# USBDroidR3.net
KiCad netlist of a schematic drawn in EAGLE
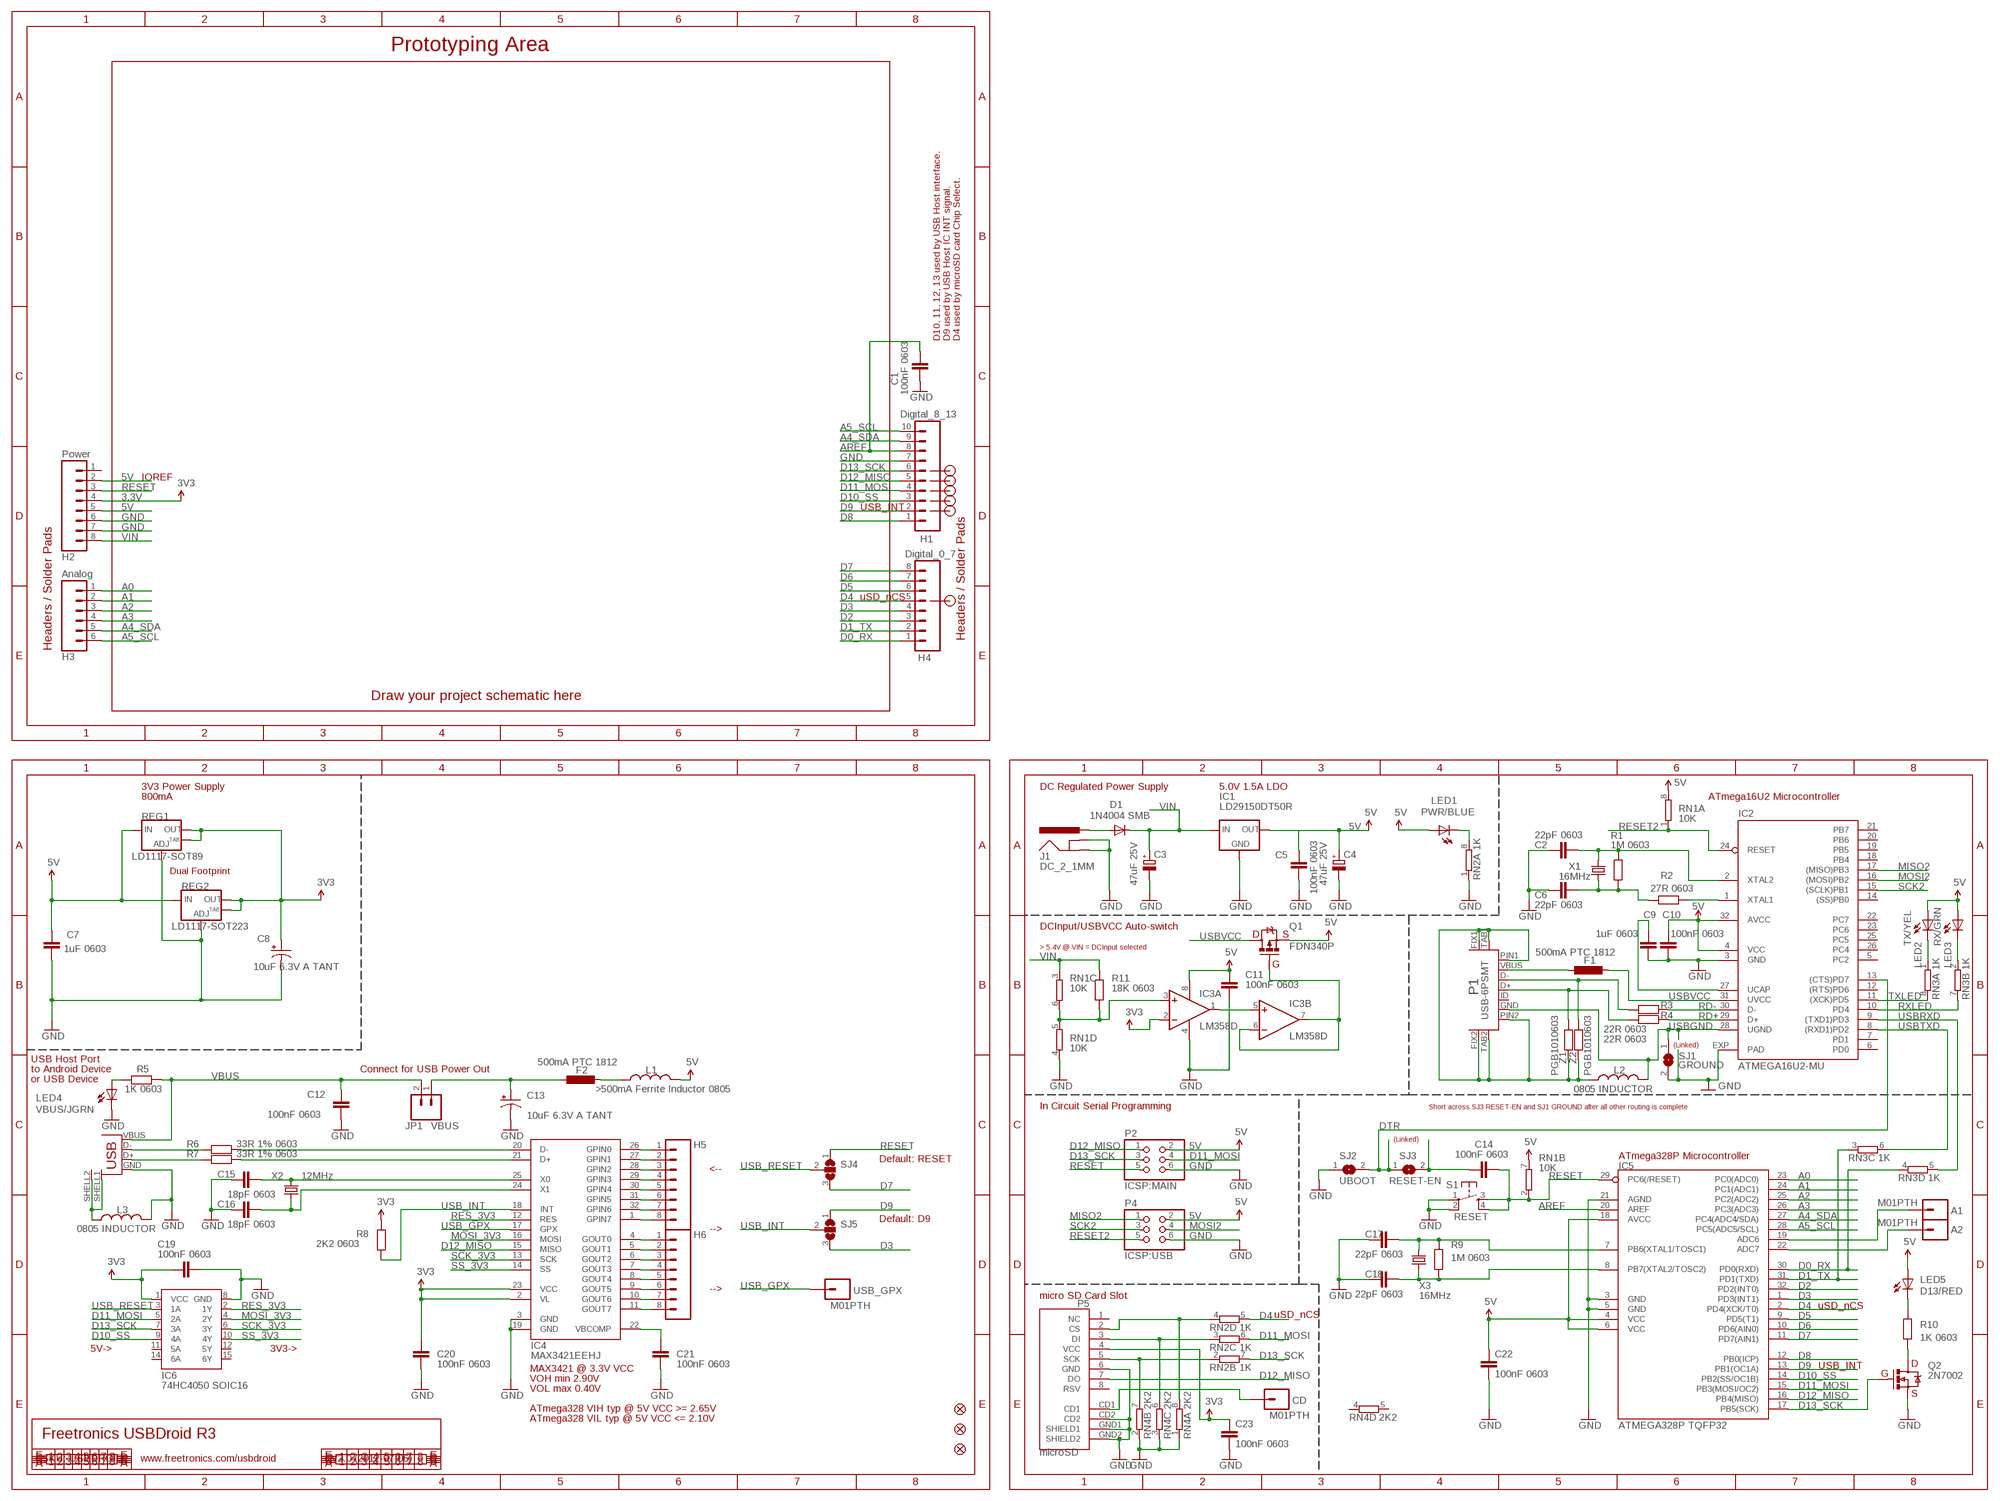
[diagram p0: schematic, sheet 1]

(export (version "E")
  (design (tool "Eeschema 10.0.6"))
  (components
    (comp (ref "A1")
      (value "M01PTH")
      (footprint "eagle-import:1X01")
      (libsource (lib "eagle-import") (part "M01PTH"))
    )
    (comp (ref "A2")
      (value "M01PTH")
      (footprint "eagle-import:1X01")
      (libsource (lib "eagle-import") (part "M01PTH"))
    )
    (comp (ref "C1")
      (value "100nF 0603")
      (footprint "eagle-import:0603")
      (libsource (lib "eagle-import") (part "CAP0603"))
    )
    (comp (ref "C2")
      (value "22pF 0603")
      (footprint "eagle-import:0603")
      (libsource (lib "eagle-import") (part "CAP0603"))
    )
    (comp (ref "C3")
      (value "47uF 25V")
      (footprint "eagle-import:PANASONIC_D")
      (libsource (lib "eagle-import") (part "CPOL-EUD"))
    )
    (comp (ref "C4")
      (value "47uF 25V")
      (footprint "eagle-import:PANASONIC_D")
      (libsource (lib "eagle-import") (part "CPOL-EUD"))
    )
    (comp (ref "C5")
      (value "100nF 0603")
      (footprint "eagle-import:0603")
      (libsource (lib "eagle-import") (part "CAP0603"))
    )
    (comp (ref "C6")
      (value "22pF 0603")
      (footprint "eagle-import:0603")
      (libsource (lib "eagle-import") (part "CAP0603"))
    )
    (comp (ref "C7")
      (value "1uF 0603")
      (footprint "eagle-import:0603")
      (libsource (lib "eagle-import") (part "CAP0603"))
    )
    (comp (ref "C8")
      (value "10uF 6.3V A TANT")
      (footprint "eagle-import:EIA3216")
      (libsource (lib "eagle-import") (part "CAP_POL1206"))
    )
    (comp (ref "C9")
      (value "1uF 0603")
      (footprint "eagle-import:0603")
      (libsource (lib "eagle-import") (part "CAP0603"))
    )
    (comp (ref "C10")
      (value "100nF 0603")
      (footprint "eagle-import:0603")
      (libsource (lib "eagle-import") (part "CAP0603"))
    )
    (comp (ref "C11")
      (value "100nF 0603")
      (footprint "eagle-import:0603")
      (libsource (lib "eagle-import") (part "CAP0603"))
    )
    (comp (ref "C12")
      (value "100nF 0603")
      (footprint "eagle-import:0603")
      (libsource (lib "eagle-import") (part "CAP0603"))
    )
    (comp (ref "C13")
      (value "10uF 6.3V A TANT")
      (footprint "eagle-import:EIA3216")
      (libsource (lib "eagle-import") (part "CAP_POL1206"))
    )
    (comp (ref "C14")
      (value "100nF 0603")
      (footprint "eagle-import:0603")
      (libsource (lib "eagle-import") (part "CAP0603"))
    )
    (comp (ref "C15")
      (value "18pF 0603")
      (footprint "eagle-import:0603")
      (libsource (lib "eagle-import") (part "CAP0603"))
    )
    (comp (ref "C16")
      (value "18pF 0603")
      (footprint "eagle-import:0603")
      (libsource (lib "eagle-import") (part "CAP0603"))
    )
    (comp (ref "C17")
      (value "22pF 0603")
      (footprint "eagle-import:0603")
      (libsource (lib "eagle-import") (part "CAP0603"))
    )
    (comp (ref "C18")
      (value "22pF 0603")
      (footprint "eagle-import:0603")
      (libsource (lib "eagle-import") (part "CAP0603"))
    )
    (comp (ref "C19")
      (value "100nF 0603")
      (footprint "eagle-import:0603")
      (libsource (lib "eagle-import") (part "CAP0603"))
    )
    (comp (ref "C20")
      (value "100nF 0603")
      (footprint "eagle-import:0603")
      (libsource (lib "eagle-import") (part "CAP0603"))
    )
    (comp (ref "C21")
      (value "100nF 0603")
      (footprint "eagle-import:0603")
      (libsource (lib "eagle-import") (part "CAP0603"))
    )
    (comp (ref "C22")
      (value "100nF 0603")
      (footprint "eagle-import:0603")
      (libsource (lib "eagle-import") (part "CAP0603"))
    )
    (comp (ref "C23")
      (value "100nF 0603")
      (footprint "eagle-import:0603")
      (libsource (lib "eagle-import") (part "CAP0603"))
    )
    (comp (ref "CD")
      (value "M01PTH")
      (footprint "eagle-import:1X01")
      (libsource (lib "eagle-import") (part "M01PTH"))
    )
    (comp (ref "D1")
      (value "1N4004 SMB")
      (footprint "eagle-import:SMB-DIODE")
      (libsource (lib "eagle-import") (part "DIODESMB"))
    )
    (comp (ref "F1")
      (value "500mA PTC 1812")
      (footprint "eagle-import:L1812")
      (libsource (lib "eagle-import") (part "L-EUL1812"))
    )
    (comp (ref "F2")
      (value "500mA PTC 1812")
      (footprint "eagle-import:L1812")
      (libsource (lib "eagle-import") (part "L-EUL1812"))
    )
    (comp (ref "FID1")
      (value "FIDUCIAL1X2.5")
      (footprint "eagle-import:FIDUCIAL-1X2.5")
      (libsource (lib "eagle-import") (part "FIDUCIAL1X2.5"))
    )
    (comp (ref "FID2")
      (value "FIDUCIAL1X2.5")
      (footprint "eagle-import:FIDUCIAL-1X2.5")
      (libsource (lib "eagle-import") (part "FIDUCIAL1X2.5"))
    )
    (comp (ref "FID3")
      (value "FIDUCIAL1X2.5")
      (footprint "eagle-import:FIDUCIAL-1X2.5")
      (libsource (lib "eagle-import") (part "FIDUCIAL1X2.5"))
    )
    (comp (ref "H1")
      (value "Digital_8_13")
      (footprint "eagle-import:1X10")
      (libsource (lib "eagle-import") (part "M100.1"))
    )
    (comp (ref "H2")
      (value "Power")
      (footprint "eagle-import:1X08")
      (libsource (lib "eagle-import") (part "freetronics-master-v1_M08"))
    )
    (comp (ref "H3")
      (value "Analog")
      (footprint "eagle-import:1X06")
      (libsource (lib "eagle-import") (part "M06SIP"))
    )
    (comp (ref "H4")
      (value "Digital_0_7")
      (footprint "eagle-import:1X08")
      (libsource (lib "eagle-import") (part "M08"))
    )
    (comp (ref "H5")
      (value "GPIN")
      (footprint "eagle-import:1X08")
      (libsource (lib "eagle-import") (part "M08"))
    )
    (comp (ref "H6")
      (value "GPIN")
      (footprint "eagle-import:1X08")
      (libsource (lib "eagle-import") (part "M08"))
    )
    (comp (ref "IC1")
      (value "LD29150DT50R")
      (footprint "eagle-import:DPACK")
      (libsource (lib "eagle-import") (part "V_REG_78XX"))
    )
    (comp (ref "IC2")
      (value "ATMEGA16U2-MU")
      (footprint "eagle-import:ATMEL_QFN32")
      (libsource (lib "eagle-import") (part "ATMEL_ATMEGA8U2-MUQFN"))
    )
    (comp (ref "IC3")
      (value "LM358D")
      (footprint "eagle-import:SO08")
      (libsource (lib "eagle-import") (part "LM358D"))
    )
    (comp (ref "IC4")
      (value "MAX3421EEHJ")
      (footprint "eagle-import:TQFP32-5MM")
      (libsource (lib "eagle-import") (part "MAX3421ESMD"))
    )
    (comp (ref "IC5")
      (value "ATMEGA328P TQFP32")
      (footprint "eagle-import:TQFP32-08")
      (libsource (lib "eagle-import") (part "AVR-MEGA8-AI"))
    )
    (comp (ref "IC6")
      (value "74HC4050 SOIC16")
      (footprint "eagle-import:SO016")
      (libsource (lib "eagle-import") (part "HEX_CONVERTER"))
    )
    (comp (ref "J1")
      (value "DC_2_1MM")
      (footprint "eagle-import:POWER_JACK_PTH")
      (libsource (lib "eagle-import") (part "POWER_JACKPTH"))
    )
    (comp (ref "JP1")
      (value "VBUS")
      (footprint "eagle-import:1X02_LOCK")
      (libsource (lib "eagle-import") (part "M02LOCK"))
    )
    (comp (ref "L1")
      (value ">500mA Ferrite Inductor 0805")
      (footprint "eagle-import:0805-LARGE")
      (libsource (lib "eagle-import") (part "INDUCTOR0805-LARGE"))
    )
    (comp (ref "L2")
      (value "0805 INDUCTOR")
      (footprint "eagle-import:0805-LARGE")
      (libsource (lib "eagle-import") (part "INDUCTOR0805-LARGE"))
    )
    (comp (ref "L3")
      (value "0805 INDUCTOR")
      (footprint "eagle-import:0805-LARGE")
      (libsource (lib "eagle-import") (part "INDUCTOR0805-LARGE"))
    )
    (comp (ref "LED1")
      (value "PWR/BLUE")
      (footprint "eagle-import:LED-0603")
      (libsource (lib "eagle-import") (part "LED0603"))
    )
    (comp (ref "LED2")
      (value "TX/YEL")
      (footprint "eagle-import:LED-0603")
      (libsource (lib "eagle-import") (part "LED0603"))
    )
    (comp (ref "LED3")
      (value "RX/GRN")
      (footprint "eagle-import:LED-0603")
      (libsource (lib "eagle-import") (part "LED0603"))
    )
    (comp (ref "LED4")
      (value "VBUS/JGRN")
      (footprint "eagle-import:LED-0603")
      (libsource (lib "eagle-import") (part "LED0603"))
    )
    (comp (ref "LED5")
      (value "D13/RED")
      (footprint "eagle-import:LED-0603")
      (libsource (lib "eagle-import") (part "LED0603"))
    )
    (comp (ref "P1")
      (value "USB-6PSMT")
      (footprint "eagle-import:USB-MICROB-MB05PMXX")
      (libsource (lib "eagle-import") (part "USB-6PSMT"))
    )
    (comp (ref "P2")
      (value "ICSP:MAIN")
      (footprint "eagle-import:2X03")
      (libsource (lib "eagle-import") (part "PINHD-2X3"))
    )
    (comp (ref "P3")
      (value "USB_")
      (footprint "eagle-import:USB-A-S-SILK-FEMALE")
      (libsource (lib "eagle-import") (part "USB_"))
    )
    (comp (ref "P4")
      (value "ICSP:USB")
      (footprint "eagle-import:2X03")
      (libsource (lib "eagle-import") (part "PINHD-2X3"))
    )
    (comp (ref "P5")
      (value "microSD")
      (footprint "eagle-import:MICRO-SD-SOCKET-PP")
      (libsource (lib "eagle-import") (part "USD-SOCKETNEW"))
    )
    (comp (ref "Q1")
      (value "FDN340P")
      (footprint "eagle-import:SOT23")
      (libsource (lib "eagle-import") (part "MOSFET-PCHANNEL"))
    )
    (comp (ref "Q2")
      (value "2N7002")
      (footprint "eagle-import:SOT23-3")
      (libsource (lib "eagle-import") (part "MOSFET-NCHANNELSMD"))
    )
    (comp (ref "R1")
      (value "1M 0603")
      (footprint "eagle-import:0603")
      (libsource (lib "eagle-import") (part "RESISTOR0603"))
    )
    (comp (ref "R2")
      (value "27R 0603")
      (footprint "eagle-import:0603")
      (libsource (lib "eagle-import") (part "RESISTOR0603"))
    )
    (comp (ref "R3")
      (value "22R 0603")
      (footprint "eagle-import:0603")
      (libsource (lib "eagle-import") (part "RESISTOR0603"))
    )
    (comp (ref "R4")
      (value "22R 0603")
      (footprint "eagle-import:0603")
      (libsource (lib "eagle-import") (part "RESISTOR0603"))
    )
    (comp (ref "R5")
      (value "1K 0603")
      (footprint "eagle-import:0603")
      (libsource (lib "eagle-import") (part "RESISTOR0603"))
    )
    (comp (ref "R6")
      (value "33R 1% 0603")
      (footprint "eagle-import:0603")
      (libsource (lib "eagle-import") (part "RESISTOR0603"))
    )
    (comp (ref "R7")
      (value "33R 1% 0603")
      (footprint "eagle-import:0603")
      (libsource (lib "eagle-import") (part "RESISTOR0603"))
    )
    (comp (ref "R8")
      (value "2K2 0603")
      (footprint "eagle-import:0603")
      (libsource (lib "eagle-import") (part "RESISTOR0603"))
    )
    (comp (ref "R9")
      (value "1M 0603")
      (footprint "eagle-import:0603")
      (libsource (lib "eagle-import") (part "RESISTOR0603"))
    )
    (comp (ref "R10")
      (value "1K 0603")
      (footprint "eagle-import:0603")
      (libsource (lib "eagle-import") (part "RESISTOR0603"))
    )
    (comp (ref "R11")
      (value "18K 0603")
      (footprint "eagle-import:0603")
      (libsource (lib "eagle-import") (part "RESISTOR0603"))
    )
    (comp (ref "REG1")
      (value "LD1117-SOT89")
      (footprint "eagle-import:SOT89")
      (libsource (lib "eagle-import") (part "V_REG_LM1117SOT89"))
    )
    (comp (ref "REG2")
      (value "LD1117-SOT223")
      (footprint "eagle-import:SOT223")
      (libsource (lib "eagle-import") (part "V_REG_LM1117SOT223"))
    )
    (comp (ref "RN1")
      (value "10K")
      (footprint "eagle-import:CAY16")
      (libsource (lib "eagle-import") (part "4R-NCAY16"))
    )
    (comp (ref "RN2")
      (value "1K")
      (footprint "eagle-import:CAY16")
      (libsource (lib "eagle-import") (part "4R-NCAY16"))
    )
    (comp (ref "RN3")
      (value "1K")
      (footprint "eagle-import:CAY16")
      (libsource (lib "eagle-import") (part "4R-NCAY16"))
    )
    (comp (ref "RN4")
      (value "2K2")
      (footprint "eagle-import:CAY16")
      (libsource (lib "eagle-import") (part "4R-NCAY16"))
    )
    (comp (ref "S1")
      (value "RESET")
      (footprint "eagle-import:TACTILE_SWITCH_SMD")
      (libsource (lib "eagle-import") (part "TAC_SWITCHSMD"))
    )
    (comp (ref "SJ1")
      (value "GROUND")
      (footprint "eagle-import:SJ")
      (libsource (lib "eagle-import") (part "SJ"))
    )
    (comp (ref "SJ2")
      (value "UBOOT")
      (footprint "eagle-import:SJ")
      (libsource (lib "eagle-import") (part "SJ"))
    )
    (comp (ref "SJ3")
      (value "RESET-EN")
      (footprint "eagle-import:SJ")
      (libsource (lib "eagle-import") (part "SJ"))
    )
    (comp (ref "SJ4")
      (value "SJ2W")
      (footprint "eagle-import:SJ_2")
      (libsource (lib "eagle-import") (part "SJ2W"))
    )
    (comp (ref "SJ5")
      (value "SJ2W")
      (footprint "eagle-import:SJ_2")
      (libsource (lib "eagle-import") (part "SJ2W"))
    )
    (comp (ref "USB_GPX")
      (value "M01PTH")
      (footprint "eagle-import:1X01")
      (libsource (lib "eagle-import") (part "M01PTH"))
    )
    (comp (ref "X1")
      (value "16MHz")
      (footprint "eagle-import:HC49U-V")
      (libsource (lib "eagle-import") (part "CRYSTALHC49UV"))
    )
    (comp (ref "X2")
      (value "12MHz")
      (footprint "eagle-import:HC49U-V")
      (libsource (lib "eagle-import") (part "CRYSTALHC49UV"))
    )
    (comp (ref "X3")
      (value "16MHz")
      (footprint "eagle-import:HC49U-V")
      (libsource (lib "eagle-import") (part "CRYSTALHC49UV"))
    )
    (comp (ref "Z1")
      (value "PGB1010603")
      (footprint "eagle-import:0603")
      (libsource (lib "eagle-import") (part "RESISTOR0603"))
    )
    (comp (ref "Z2")
      (value "PGB1010603")
      (footprint "eagle-import:0603")
      (libsource (lib "eagle-import") (part "RESISTOR0603"))
    )
  )
  (nets
    (net (code "1") (name "/A0") (class "Default")
      (node (ref "H3") (pin "1") (pinfunction "1_1") (pintype "passive"))
      (node (ref "IC5") (pin "23") (pinfunction "PC0(ADC0)_23") (pintype "bidirectional"))
    )
    (net (code "2") (name "/A1") (class "Default")
      (node (ref "H3") (pin "2") (pinfunction "2_2") (pintype "passive"))
      (node (ref "IC5") (pin "24") (pinfunction "PC1(ADC1)_24") (pintype "bidirectional"))
    )
    (net (code "3") (name "/A2") (class "Default")
      (node (ref "H3") (pin "3") (pinfunction "3_3") (pintype "passive"))
      (node (ref "IC5") (pin "25") (pinfunction "PC2(ADC2)_25") (pintype "bidirectional"))
    )
    (net (code "4") (name "/A3") (class "Default")
      (node (ref "H3") (pin "4") (pinfunction "4_4") (pintype "passive"))
      (node (ref "IC5") (pin "26") (pinfunction "PC3(ADC3)_26") (pintype "bidirectional"))
    )
    (net (code "5") (name "/A4_SDA") (class "Default")
      (node (ref "H1") (pin "9") (pinfunction "9_9") (pintype "passive"))
      (node (ref "H3") (pin "5") (pinfunction "5_5") (pintype "passive"))
      (node (ref "IC5") (pin "27") (pinfunction "PC4(ADC4/SDA)_27") (pintype "bidirectional"))
    )
    (net (code "6") (name "/A5_SCL") (class "Default")
      (node (ref "H1") (pin "10") (pinfunction "10_10") (pintype "passive"))
      (node (ref "H3") (pin "6") (pinfunction "6_6") (pintype "passive"))
      (node (ref "IC5") (pin "28") (pinfunction "PC5(ADC5/SCL)_28") (pintype "bidirectional"))
    )
    (net (code "7") (name "/AREF") (class "Default")
      (node (ref "C1") (pin "1") (pinfunction "1_1") (pintype "passive"))
      (node (ref "H1") (pin "8") (pinfunction "8_8") (pintype "passive"))
      (node (ref "IC5") (pin "20") (pinfunction "AREF_20") (pintype "bidirectional"))
    )
    (net (code "8") (name "/D0_RX") (class "Default")
      (node (ref "H4") (pin "1") (pinfunction "1_1") (pintype "passive"))
      (node (ref "IC5") (pin "30") (pinfunction "PD0(RXD)_30") (pintype "bidirectional"))
      (node (ref "RN3") (pin "4") (pinfunction "1_4") (pintype "passive"))
    )
    (net (code "9") (name "/D1_TX") (class "Default")
      (node (ref "H4") (pin "2") (pinfunction "2_2") (pintype "passive"))
      (node (ref "IC5") (pin "31") (pinfunction "PD1(TXD)_31") (pintype "bidirectional"))
      (node (ref "RN3") (pin "3") (pinfunction "1_3") (pintype "passive"))
    )
    (net (code "10") (name "/D2") (class "Default")
      (node (ref "H4") (pin "3") (pinfunction "3_3") (pintype "passive"))
      (node (ref "IC5") (pin "32") (pinfunction "PD2(INT0)_32") (pintype "bidirectional"))
    )
    (net (code "11") (name "/D3") (class "Default")
      (node (ref "H4") (pin "4") (pinfunction "4_4") (pintype "passive"))
      (node (ref "IC5") (pin "1") (pinfunction "PD3(INT1)_1") (pintype "bidirectional"))
      (node (ref "SJ5") (pin "3") (pinfunction "3_3") (pintype "passive"))
    )
    (net (code "12") (name "/D4") (class "Default")
      (node (ref "H4") (pin "5") (pinfunction "5_5") (pintype "passive"))
      (node (ref "IC5") (pin "2") (pinfunction "PD4(XCK/T0)_2") (pintype "bidirectional"))
      (node (ref "RN2") (pin "5") (pinfunction "2_5") (pintype "passive"))
    )
    (net (code "13") (name "/D5") (class "Default")
      (node (ref "H4") (pin "6") (pinfunction "6_6") (pintype "passive"))
      (node (ref "IC5") (pin "9") (pinfunction "PD5(T1)_9") (pintype "bidirectional"))
    )
    (net (code "14") (name "/D6") (class "Default")
      (node (ref "H4") (pin "7") (pinfunction "7_7") (pintype "passive"))
      (node (ref "IC5") (pin "10") (pinfunction "PD6(AIN0)_10") (pintype "bidirectional"))
    )
    (net (code "15") (name "/D7") (class "Default")
      (node (ref "H4") (pin "8") (pinfunction "8_8") (pintype "passive"))
      (node (ref "IC5") (pin "11") (pinfunction "PD7(AIN1)_11") (pintype "bidirectional"))
      (node (ref "SJ4") (pin "3") (pinfunction "3_3") (pintype "passive"))
    )
    (net (code "16") (name "/D8") (class "Default")
      (node (ref "H1") (pin "1") (pinfunction "1_1") (pintype "passive"))
      (node (ref "IC5") (pin "12") (pinfunction "PB0(ICP)_12") (pintype "bidirectional"))
    )
    (net (code "17") (name "/D9") (class "Default")
      (node (ref "H1") (pin "2") (pinfunction "2_2") (pintype "passive"))
      (node (ref "IC5") (pin "13") (pinfunction "PB1(OC1A)_13") (pintype "bidirectional"))
      (node (ref "SJ5") (pin "1") (pinfunction "1_1") (pintype "passive"))
    )
    (net (code "18") (name "/D10_SS") (class "Default")
      (node (ref "H1") (pin "3") (pinfunction "3_3") (pintype "passive"))
      (node (ref "IC5") (pin "14") (pinfunction "PB2(SS/OC1B)_14") (pintype "bidirectional"))
      (node (ref "IC6") (pin "9") (pinfunction "4A_9") (pintype "bidirectional"))
    )
    (net (code "19") (name "/D11_MOSI") (class "Default")
      (node (ref "H1") (pin "4") (pinfunction "4_4") (pintype "passive"))
      (node (ref "IC5") (pin "15") (pinfunction "PB3(MOSI/OC2)_15") (pintype "bidirectional"))
      (node (ref "IC6") (pin "5") (pinfunction "2A_5") (pintype "bidirectional"))
      (node (ref "P2") (pin "4") (pinfunction "4_4") (pintype "passive"))
      (node (ref "RN2") (pin "6") (pinfunction "2_6") (pintype "passive"))
    )
    (net (code "20") (name "/D12_MISO") (class "Default")
      (node (ref "H1") (pin "5") (pinfunction "5_5") (pintype "passive"))
      (node (ref "IC4") (pin "15") (pinfunction "MISO_15") (pintype "bidirectional"))
      (node (ref "IC5") (pin "16") (pinfunction "PB4(MISO)_16") (pintype "bidirectional"))
      (node (ref "P2") (pin "1") (pinfunction "1_1") (pintype "passive"))
      (node (ref "P5") (pin "7") (pinfunction "DO_7") (pintype "bidirectional"))
    )
    (net (code "21") (name "/D13_SCK") (class "Default")
      (node (ref "H1") (pin "6") (pinfunction "6_6") (pintype "passive"))
      (node (ref "IC5") (pin "17") (pinfunction "PB5(SCK)_17") (pintype "bidirectional"))
      (node (ref "IC6") (pin "7") (pinfunction "3A_7") (pintype "bidirectional"))
      (node (ref "P2") (pin "3") (pinfunction "3_3") (pintype "passive"))
      (node (ref "Q2") (pin "1") (pinfunction "G_1") (pintype "passive"))
      (node (ref "RN2") (pin "7") (pinfunction "2_7") (pintype "passive"))
    )
    (net (code "22") (name "/DTR") (class "Default")
      (node (ref "IC2") (pin "13") (pinfunction "(CTS)PD7_13") (pintype "bidirectional"))
      (node (ref "SJ2") (pin "2") (pinfunction "2_2") (pintype "passive"))
      (node (ref "SJ3") (pin "1") (pinfunction "1_1") (pintype "passive"))
    )
    (net (code "23") (name "/MISO2") (class "Default")
      (node (ref "IC2") (pin "17") (pinfunction "(MISO)PB3_17") (pintype "bidirectional"))
      (node (ref "P4") (pin "1") (pinfunction "1_1") (pintype "passive"))
    )
    (net (code "24") (name "/MOSI2") (class "Default")
      (node (ref "IC2") (pin "16") (pinfunction "(MOSI)PB2_16") (pintype "bidirectional"))
      (node (ref "P4") (pin "4") (pinfunction "4_4") (pintype "passive"))
    )
    (net (code "25") (name "/MOSI_3V3") (class "Default")
      (node (ref "IC4") (pin "16") (pinfunction "MOSI_16") (pintype "bidirectional"))
      (node (ref "IC6") (pin "4") (pinfunction "2Y_4") (pintype "bidirectional"))
    )
    (net (code "26") (name "/RD+") (class "Default")
      (node (ref "IC2") (pin "29") (pinfunction "D+_29") (pintype "bidirectional"))
      (node (ref "R4") (pin "1") (pinfunction "1_1") (pintype "passive"))
    )
    (net (code "27") (name "/RD-") (class "Default")
      (node (ref "IC2") (pin "30") (pinfunction "D-_30") (pintype "bidirectional"))
      (node (ref "R3") (pin "1") (pinfunction "1_1") (pintype "passive"))
    )
    (net (code "28") (name "/RESET") (class "Default")
      (node (ref "C14") (pin "2") (pinfunction "2_2") (pintype "passive"))
      (node (ref "H2") (pin "3") (pinfunction "3_3") (pintype "passive"))
      (node (ref "IC5") (pin "29") (pinfunction "PC6(/RESET)_29") (pintype "bidirectional"))
      (node (ref "P2") (pin "5") (pinfunction "5_5") (pintype "passive"))
      (node (ref "RN1") (pin "2") (pinfunction "1_2") (pintype "passive"))
      (node (ref "S1") (pin "3") (pinfunction "3_3") (pintype "passive"))
      (node (ref "S1") (pin "4") (pinfunction "4_4") (pintype "passive"))
      (node (ref "SJ4") (pin "1") (pinfunction "1_1") (pintype "passive"))
    )
    (net (code "29") (name "/RESET2") (class "Default")
      (node (ref "IC2") (pin "24") (pinfunction "RESET_24") (pintype "input"))
      (node (ref "P4") (pin "5") (pinfunction "5_5") (pintype "passive"))
      (node (ref "RN1") (pin "1") (pinfunction "1_1") (pintype "passive"))
    )
    (net (code "30") (name "/RES_3V3") (class "Default")
      (node (ref "IC4") (pin "12") (pinfunction "RES_12") (pintype "bidirectional"))
      (node (ref "IC6") (pin "2") (pinfunction "1Y_2") (pintype "bidirectional"))
    )
    (net (code "31") (name "/RXLED") (class "Default")
      (node (ref "IC2") (pin "10") (pinfunction "PD4_10") (pintype "bidirectional"))
      (node (ref "RN3") (pin "7") (pinfunction "2_7") (pintype "passive"))
    )
    (net (code "32") (name "/SCK2") (class "Default")
      (node (ref "IC2") (pin "15") (pinfunction "(SCLK)PB1_15") (pintype "bidirectional"))
      (node (ref "P4") (pin "3") (pinfunction "3_3") (pintype "passive"))
    )
    (net (code "33") (name "/SCK_3V3") (class "Default")
      (node (ref "IC4") (pin "13") (pinfunction "SCK_13") (pintype "bidirectional"))
      (node (ref "IC6") (pin "6") (pinfunction "3Y_6") (pintype "bidirectional"))
    )
    (net (code "34") (name "/SS_3V3") (class "Default")
      (node (ref "IC4") (pin "14") (pinfunction "SS_14") (pintype "bidirectional"))
      (node (ref "IC6") (pin "10") (pinfunction "4Y_10") (pintype "bidirectional"))
    )
    (net (code "35") (name "/TXLED") (class "Default")
      (node (ref "IC2") (pin "11") (pinfunction "(XCK)PD5_11") (pintype "bidirectional"))
      (node (ref "RN3") (pin "8") (pinfunction "2_8") (pintype "passive"))
    )
    (net (code "36") (name "/USBGND") (class "Default")
      (node (ref "IC2") (pin "28") (pinfunction "UGND_28") (pintype "power_in"))
      (node (ref "L2") (pin "2") (pinfunction "2_2") (pintype "passive"))
      (node (ref "P1") (pin "GND") (pinfunction "GND_GND") (pintype "bidirectional"))
      (node (ref "SJ1") (pin "1") (pinfunction "1_1") (pintype "passive"))
    )
    (net (code "37") (name "/USBRXD") (class "Default")
      (node (ref "IC2") (pin "9") (pinfunction "(TXD1)PD3_9") (pintype "bidirectional"))
      (node (ref "RN3") (pin "5") (pinfunction "2_5") (pintype "passive"))
    )
    (net (code "38") (name "/USBTXD") (class "Default")
      (node (ref "IC2") (pin "8") (pinfunction "(RXD1)PD2_8") (pintype "bidirectional"))
      (node (ref "RN3") (pin "6") (pinfunction "2_6") (pintype "passive"))
    )
    (net (code "39") (name "/USBVCC") (class "Default")
      (node (ref "F1") (pin "2") (pinfunction "2_2") (pintype "passive"))
      (node (ref "IC2") (pin "31") (pinfunction "UVCC_31") (pintype "power_in"))
      (node (ref "Q1") (pin "3") (pinfunction "D_3") (pintype "passive"))
    )
    (net (code "40") (name "/USB_GPX") (class "Default")
      (node (ref "IC4") (pin "17") (pinfunction "GPX_17") (pintype "bidirectional"))
      (node (ref "USB_GPX") (pin "1") (pinfunction "1_1") (pintype "passive"))
    )
    (net (code "41") (name "/USB_INT") (class "Default")
      (node (ref "IC4") (pin "18") (pinfunction "INT_18") (pintype "bidirectional"))
      (node (ref "R8") (pin "2") (pinfunction "2_2") (pintype "passive"))
      (node (ref "SJ5") (pin "2") (pinfunction "2_2") (pintype "passive"))
    )
    (net (code "42") (name "/USB_RESET") (class "Default")
      (node (ref "IC6") (pin "3") (pinfunction "1A_3") (pintype "bidirectional"))
      (node (ref "SJ4") (pin "2") (pinfunction "2_2") (pintype "passive"))
    )
    (net (code "43") (name "/VBUS") (class "Default")
      (node (ref "C12") (pin "2") (pinfunction "2_2") (pintype "passive"))
      (node (ref "JP1") (pin "2") (pinfunction "2_2") (pintype "passive"))
      (node (ref "P3") (pin "VBUS") (pinfunction "VBUS_VBUS") (pintype "bidirectional"))
      (node (ref "R5") (pin "2") (pinfunction "2_2") (pintype "passive"))
    )
    (net (code "44") (name "/VIN") (class "Default")
      (node (ref "C3") (pin "+") (pinfunction "+_+") (pintype "passive"))
      (node (ref "D1") (pin "C") (pinfunction "C_C") (pintype "passive"))
      (node (ref "H2") (pin "8") (pinfunction "8_8") (pintype "passive"))
      (node (ref "IC1") (pin "1") (pinfunction "IN_1") (pintype "input"))
      (node (ref "R11") (pin "2") (pinfunction "2_2") (pintype "passive"))
      (node (ref "RN1") (pin "3") (pinfunction "1_3") (pintype "passive"))
    )
    (net (code "45") (name "3V3") (class "Default")
      (node (ref "C19") (pin "2") (pinfunction "2_2") (pintype "passive"))
      (node (ref "C20") (pin "2") (pinfunction "2_2") (pintype "passive"))
      (node (ref "C23") (pin "1") (pinfunction "1_1") (pintype "passive"))
      (node (ref "C8") (pin "A") (pinfunction "+_A") (pintype "passive"))
      (node (ref "H2") (pin "4") (pinfunction "4_4") (pintype "passive"))
      (node (ref "IC3") (pin "2") (pinfunction "-IN_2") (pintype "input"))
      (node (ref "IC4") (pin "2") (pinfunction "VL_2") (pintype "bidirectional"))
      (node (ref "IC4") (pin "23") (pinfunction "VCC_23") (pintype "bidirectional"))
      (node (ref "IC6") (pin "1") (pinfunction "VCC_1") (pintype "bidirectional"))
      (node (ref "P5") (pin "4") (pinfunction "VCC_4") (pintype "bidirectional"))
      (node (ref "R8") (pin "1") (pinfunction "1_1") (pintype "passive"))
      (node (ref "REG1") (pin "2") (pinfunction "OUT_2") (pintype "output"))
      (node (ref "REG1") (pin "4") (pinfunction "OUT_4") (pintype "output"))
      (node (ref "REG2") (pin "2") (pinfunction "OUT_2") (pintype "output"))
      (node (ref "REG2") (pin "4") (pinfunction "OUT_4") (pintype "output"))
    )
    (net (code "46") (name "5V") (class "Default")
      (node (ref "C10") (pin "1") (pinfunction "1_1") (pintype "passive"))
      (node (ref "C11") (pin "1") (pinfunction "1_1") (pintype "passive"))
      (node (ref "C22") (pin "1") (pinfunction "1_1") (pintype "passive"))
      (node (ref "C4") (pin "+") (pinfunction "+_+") (pintype "passive"))
      (node (ref "C5") (pin "1") (pinfunction "1_1") (pintype "passive"))
      (node (ref "C7") (pin "1") (pinfunction "1_1") (pintype "passive"))
      (node (ref "H2") (pin "2") (pinfunction "2_2") (pintype "passive"))
      (node (ref "H2") (pin "5") (pinfunction "5_5") (pintype "passive"))
      (node (ref "IC1") (pin "3") (pinfunction "OUT_3") (pintype "output"))
      (node (ref "IC2") (pin "32") (pinfunction "AVCC_32") (pintype "power_in"))
      (node (ref "IC2") (pin "4") (pinfunction "VCC_4") (pintype "power_in"))
      (node (ref "IC3") (pin "8") (pinfunction "V+_8") (pintype "power_in"))
      (node (ref "IC5") (pin "18") (pinfunction "AVCC_18") (pintype "bidirectional"))
      (node (ref "IC5") (pin "4") (pinfunction "VCC_4") (pintype "bidirectional"))
      (node (ref "IC5") (pin "6") (pinfunction "VCC_6") (pintype "bidirectional"))
      (node (ref "L1") (pin "2") (pinfunction "2_2") (pintype "passive"))
      (node (ref "LED1") (pin "A") (pinfunction "A_A") (pintype "passive"))
      (node (ref "LED2") (pin "A") (pinfunction "A_A") (pintype "passive"))
      (node (ref "LED3") (pin "A") (pinfunction "A_A") (pintype "passive"))
      (node (ref "LED5") (pin "A") (pinfunction "A_A") (pintype "passive"))
      (node (ref "P2") (pin "2") (pinfunction "2_2") (pintype "passive"))
      (node (ref "P4") (pin "2") (pinfunction "2_2") (pintype "passive"))
      (node (ref "Q1") (pin "2") (pinfunction "S_2") (pintype "passive"))
      (node (ref "REG1") (pin "3") (pinfunction "IN_3") (pintype "input"))
      (node (ref "REG2") (pin "3") (pinfunction "IN_3") (pintype "input"))
      (node (ref "RN1") (pin "7") (pinfunction "2_7") (pintype "passive"))
      (node (ref "RN1") (pin "8") (pinfunction "2_8") (pintype "passive"))
    )
    (net (code "47") (name "GND") (class "Default")
      (node (ref "C1") (pin "2") (pinfunction "2_2") (pintype "passive"))
      (node (ref "C10") (pin "2") (pinfunction "2_2") (pintype "passive"))
      (node (ref "C11") (pin "2") (pinfunction "2_2") (pintype "passive"))
      (node (ref "C12") (pin "1") (pinfunction "1_1") (pintype "passive"))
      (node (ref "C13") (pin "C") (pinfunction "-_C") (pintype "passive"))
      (node (ref "C15") (pin "1") (pinfunction "1_1") (pintype "passive"))
      (node (ref "C16") (pin "1") (pinfunction "1_1") (pintype "passive"))
      (node (ref "C17") (pin "1") (pinfunction "1_1") (pintype "passive"))
      (node (ref "C18") (pin "1") (pinfunction "1_1") (pintype "passive"))
      (node (ref "C19") (pin "1") (pinfunction "1_1") (pintype "passive"))
      (node (ref "C2") (pin "1") (pinfunction "1_1") (pintype "passive"))
      (node (ref "C20") (pin "1") (pinfunction "1_1") (pintype "passive"))
      (node (ref "C21") (pin "1") (pinfunction "1_1") (pintype "passive"))
      (node (ref "C22") (pin "2") (pinfunction "2_2") (pintype "passive"))
      (node (ref "C23") (pin "2") (pinfunction "2_2") (pintype "passive"))
      (node (ref "C3") (pin "-") (pinfunction "-_-") (pintype "passive"))
      (node (ref "C4") (pin "-") (pinfunction "-_-") (pintype "passive"))
      (node (ref "C5") (pin "2") (pinfunction "2_2") (pintype "passive"))
      (node (ref "C6") (pin "1") (pinfunction "1_1") (pintype "passive"))
      (node (ref "C7") (pin "2") (pinfunction "2_2") (pintype "passive"))
      (node (ref "C8") (pin "C") (pinfunction "-_C") (pintype "passive"))
      (node (ref "C9") (pin "2") (pinfunction "2_2") (pintype "passive"))
      (node (ref "H1") (pin "7") (pinfunction "7_7") (pintype "passive"))
      (node (ref "H2") (pin "6") (pinfunction "6_6") (pintype "passive"))
      (node (ref "H2") (pin "7") (pinfunction "7_7") (pintype "passive"))
      (node (ref "IC1") (pin "2") (pinfunction "GND_2") (pintype "input"))
      (node (ref "IC2") (pin "3") (pinfunction "GND_3") (pintype "power_in"))
      (node (ref "IC2") (pin "EXP") (pinfunction "PAD_EXP") (pintype "power_in"))
      (node (ref "IC3") (pin "4") (pinfunction "V-_4") (pintype "power_in"))
      (node (ref "IC4") (pin "19") (pinfunction "GND_19") (pintype "bidirectional"))
      (node (ref "IC4") (pin "3") (pinfunction "GND_3") (pintype "bidirectional"))
      (node (ref "IC5") (pin "21") (pinfunction "AGND_21") (pintype "bidirectional"))
      (node (ref "IC5") (pin "3") (pinfunction "GND_3") (pintype "bidirectional"))
      (node (ref "IC5") (pin "5") (pinfunction "GND_5") (pintype "bidirectional"))
      (node (ref "IC6") (pin "8") (pinfunction "GND_8") (pintype "bidirectional"))
      (node (ref "J1") (pin "GND") (pinfunction "GND_GND") (pintype "bidirectional"))
      (node (ref "J1") (pin "GNDBREAK") (pinfunction "GNDBREAK_GNDBREAK") (pintype "bidirectional"))
      (node (ref "L3") (pin "2") (pinfunction "2_2") (pintype "passive"))
      (node (ref "LED4") (pin "C") (pinfunction "C_C") (pintype "passive"))
      (node (ref "P2") (pin "6") (pinfunction "6_6") (pintype "passive"))
      (node (ref "P3") (pin "GND") (pinfunction "GND_GND") (pintype "bidirectional"))
      (node (ref "P4") (pin "6") (pinfunction "6_6") (pintype "passive"))
      (node (ref "P5") (pin "6") (pinfunction "GND_6") (pintype "bidirectional"))
      (node (ref "P5") (pin "CD2") (pinfunction "CD2_CD2") (pintype "bidirectional"))
      (node (ref "P5") (pin "GND1") (pinfunction "SHIELD1_GND1") (pintype "bidirectional"))
      (node (ref "P5") (pin "GND2") (pinfunction "SHIELD2_GND2") (pintype "bidirectional"))
      (node (ref "Q2") (pin "2") (pinfunction "S_2") (pintype "passive"))
      (node (ref "REG1") (pin "1") (pinfunction "ADJ_1") (pintype "input"))
      (node (ref "REG2") (pin "1") (pinfunction "ADJ_1") (pintype "input"))
      (node (ref "RN1") (pin "4") (pinfunction "1_4") (pintype "passive"))
      (node (ref "RN2") (pin "1") (pinfunction "1_1") (pintype "passive"))
      (node (ref "RN4") (pin "1") (pinfunction "1_1") (pintype "passive"))
      (node (ref "RN4") (pin "2") (pinfunction "1_2") (pintype "passive"))
      (node (ref "RN4") (pin "3") (pinfunction "1_3") (pintype "passive"))
      (node (ref "S1") (pin "1") (pinfunction "1_1") (pintype "passive"))
      (node (ref "S1") (pin "2") (pinfunction "2_2") (pintype "passive"))
      (node (ref "SJ1") (pin "2") (pinfunction "2_2") (pintype "passive"))
      (node (ref "SJ2") (pin "1") (pinfunction "1_1") (pintype "passive"))
    )
    (net (code "48") (name "Net-(C6-Pad2)") (class "Default")
      (node (ref "C6") (pin "2") (pinfunction "2_2") (pintype "passive"))
      (node (ref "R1") (pin "1") (pinfunction "1_1") (pintype "passive"))
      (node (ref "R2") (pin "2") (pinfunction "2_2") (pintype "passive"))
      (node (ref "X1") (pin "1") (pinfunction "1_1") (pintype "passive"))
    )
    (net (code "49") (name "Net-(C13-+)") (class "Default")
      (node (ref "C13") (pin "A") (pinfunction "+_A") (pintype "passive"))
      (node (ref "F2") (pin "1") (pinfunction "1_1") (pintype "passive"))
      (node (ref "JP1") (pin "1") (pinfunction "1_1") (pintype "passive"))
    )
    (net (code "50") (name "Net-(C14-Pad1)") (class "Default")
      (node (ref "C14") (pin "1") (pinfunction "1_1") (pintype "passive"))
      (node (ref "SJ3") (pin "2") (pinfunction "2_2") (pintype "passive"))
    )
    (net (code "51") (name "Net-(CD-Pad1)") (class "Default")
      (node (ref "CD") (pin "1") (pinfunction "1_1") (pintype "passive"))
      (node (ref "P5") (pin "CD1") (pinfunction "CD1_CD1") (pintype "bidirectional"))
    )
    (net (code "52") (name "Net-(D1-PadA)") (class "Default")
      (node (ref "D1") (pin "A") (pinfunction "A_A") (pintype "passive"))
      (node (ref "J1") (pin "PWR") (pinfunction "PWR_PWR") (pintype "bidirectional"))
    )
    (net (code "53") (name "Net-(F1-Pad1)") (class "Default")
      (node (ref "F1") (pin "1") (pinfunction "1_1") (pintype "passive"))
      (node (ref "P1") (pin "VBUS") (pinfunction "VBUS_VBUS") (pintype "bidirectional"))
    )
    (net (code "54") (name "Net-(F2-Pad2)") (class "Default")
      (node (ref "F2") (pin "2") (pinfunction "2_2") (pintype "passive"))
      (node (ref "L1") (pin "1") (pinfunction "1_1") (pintype "passive"))
    )
    (net (code "55") (name "Net-(IC2-UCAP)") (class "Default")
      (node (ref "C9") (pin "1") (pinfunction "1_1") (pintype "passive"))
      (node (ref "IC2") (pin "27") (pinfunction "UCAP_27") (pintype "passive"))
    )
    (net (code "56") (name "Net-(IC2-XTAL1)") (class "Default")
      (node (ref "IC2") (pin "1") (pinfunction "XTAL1_1") (pintype "bidirectional"))
      (node (ref "R2") (pin "1") (pinfunction "1_1") (pintype "passive"))
    )
    (net (code "57") (name "Net-(IC2-XTAL2)") (class "Default")
      (node (ref "C2") (pin "2") (pinfunction "2_2") (pintype "passive"))
      (node (ref "IC2") (pin "2") (pinfunction "XTAL2_2") (pintype "bidirectional"))
      (node (ref "R1") (pin "2") (pinfunction "2_2") (pintype "passive"))
      (node (ref "X1") (pin "2") (pinfunction "2_2") (pintype "passive"))
    )
    (net (code "58") (name "Net-(IC3A-+IN)") (class "Default")
      (node (ref "IC3") (pin "3") (pinfunction "+IN_3") (pintype "input"))
      (node (ref "R11") (pin "1") (pinfunction "1_1") (pintype "passive"))
      (node (ref "RN1") (pin "5") (pinfunction "2_5") (pintype "passive"))
      (node (ref "RN1") (pin "6") (pinfunction "2_6") (pintype "passive"))
    )
    (net (code "59") (name "Net-(IC3A-OUT)") (class "Default")
      (node (ref "IC3") (pin "1") (pinfunction "OUT_1") (pintype "output"))
      (node (ref "IC3") (pin "5") (pinfunction "+IN_5") (pintype "input"))
    )
    (net (code "60") (name "Net-(IC3B--IN)") (class "Default")
      (node (ref "IC3") (pin "6") (pinfunction "-IN_6") (pintype "input"))
      (node (ref "IC3") (pin "7") (pinfunction "OUT_7") (pintype "output"))
      (node (ref "Q1") (pin "1") (pinfunction "G_1") (pintype "passive"))
    )
    (net (code "61") (name "Net-(IC4-D+)") (class "Default")
      (node (ref "IC4") (pin "21") (pinfunction "D+_21") (pintype "bidirectional"))
      (node (ref "R7") (pin "1") (pinfunction "1_1") (pintype "passive"))
    )
    (net (code "62") (name "Net-(IC4-D-)") (class "Default")
      (node (ref "IC4") (pin "20") (pinfunction "D-_20") (pintype "bidirectional"))
      (node (ref "R6") (pin "1") (pinfunction "1_1") (pintype "passive"))
    )
    (net (code "63") (name "Net-(IC4-GOUT0)") (class "Default")
      (node (ref "H6") (pin "1") (pinfunction "1_1") (pintype "passive"))
      (node (ref "IC4") (pin "4") (pinfunction "GOUT0_4") (pintype "bidirectional"))
    )
    (net (code "64") (name "Net-(IC4-GOUT1)") (class "Default")
      (node (ref "H6") (pin "2") (pinfunction "2_2") (pintype "passive"))
      (node (ref "IC4") (pin "5") (pinfunction "GOUT1_5") (pintype "bidirectional"))
    )
    (net (code "65") (name "Net-(IC4-GOUT2)") (class "Default")
      (node (ref "H6") (pin "3") (pinfunction "3_3") (pintype "passive"))
      (node (ref "IC4") (pin "6") (pinfunction "GOUT2_6") (pintype "bidirectional"))
    )
    (net (code "66") (name "Net-(IC4-GOUT3)") (class "Default")
      (node (ref "H6") (pin "4") (pinfunction "4_4") (pintype "passive"))
      (node (ref "IC4") (pin "7") (pinfunction "GOUT3_7") (pintype "bidirectional"))
    )
    (net (code "67") (name "Net-(IC4-GOUT4)") (class "Default")
      (node (ref "H6") (pin "5") (pinfunction "5_5") (pintype "passive"))
      (node (ref "IC4") (pin "8") (pinfunction "GOUT4_8") (pintype "bidirectional"))
    )
    (net (code "68") (name "Net-(IC4-GOUT5)") (class "Default")
      (node (ref "H6") (pin "6") (pinfunction "6_6") (pintype "passive"))
      (node (ref "IC4") (pin "9") (pinfunction "GOUT5_9") (pintype "bidirectional"))
    )
    (net (code "69") (name "Net-(IC4-GOUT6)") (class "Default")
      (node (ref "H6") (pin "7") (pinfunction "7_7") (pintype "passive"))
      (node (ref "IC4") (pin "10") (pinfunction "GOUT6_10") (pintype "bidirectional"))
    )
    (net (code "70") (name "Net-(IC4-GOUT7)") (class "Default")
      (node (ref "H6") (pin "8") (pinfunction "8_8") (pintype "passive"))
      (node (ref "IC4") (pin "11") (pinfunction "GOUT7_11") (pintype "bidirectional"))
    )
    (net (code "71") (name "Net-(IC4-GPIN0)") (class "Default")
      (node (ref "H5") (pin "1") (pinfunction "1_1") (pintype "passive"))
      (node (ref "IC4") (pin "26") (pinfunction "GPIN0_26") (pintype "bidirectional"))
    )
    (net (code "72") (name "Net-(IC4-GPIN1)") (class "Default")
      (node (ref "H5") (pin "2") (pinfunction "2_2") (pintype "passive"))
      (node (ref "IC4") (pin "27") (pinfunction "GPIN1_27") (pintype "bidirectional"))
    )
    (net (code "73") (name "Net-(IC4-GPIN2)") (class "Default")
      (node (ref "H5") (pin "3") (pinfunction "3_3") (pintype "passive"))
      (node (ref "IC4") (pin "28") (pinfunction "GPIN2_28") (pintype "bidirectional"))
    )
    (net (code "74") (name "Net-(IC4-GPIN3)") (class "Default")
      (node (ref "H5") (pin "4") (pinfunction "4_4") (pintype "passive"))
      (node (ref "IC4") (pin "29") (pinfunction "GPIN3_29") (pintype "bidirectional"))
    )
    (net (code "75") (name "Net-(IC4-GPIN4)") (class "Default")
      (node (ref "H5") (pin "5") (pinfunction "5_5") (pintype "passive"))
      (node (ref "IC4") (pin "30") (pinfunction "GPIN4_30") (pintype "bidirectional"))
    )
    (net (code "76") (name "Net-(IC4-GPIN5)") (class "Default")
      (node (ref "H5") (pin "6") (pinfunction "6_6") (pintype "passive"))
      (node (ref "IC4") (pin "31") (pinfunction "GPIN5_31") (pintype "bidirectional"))
    )
    (net (code "77") (name "Net-(IC4-GPIN6)") (class "Default")
      (node (ref "H5") (pin "7") (pinfunction "7_7") (pintype "passive"))
      (node (ref "IC4") (pin "32") (pinfunction "GPIN6_32") (pintype "bidirectional"))
    )
    (net (code "78") (name "Net-(IC4-GPIN7)") (class "Default")
      (node (ref "H5") (pin "8") (pinfunction "8_8") (pintype "passive"))
      (node (ref "IC4") (pin "1") (pinfunction "GPIN7_1") (pintype "bidirectional"))
    )
    (net (code "79") (name "Net-(IC4-VBCOMP)") (class "Default")
      (node (ref "C21") (pin "2") (pinfunction "2_2") (pintype "passive"))
      (node (ref "IC4") (pin "22") (pinfunction "VBCOMP_22") (pintype "bidirectional"))
    )
    (net (code "80") (name "Net-(IC4-X0)") (class "Default")
      (node (ref "C15") (pin "2") (pinfunction "2_2") (pintype "passive"))
      (node (ref "IC4") (pin "25") (pinfunction "X0_25") (pintype "bidirectional"))
      (node (ref "X2") (pin "2") (pinfunction "2_2") (pintype "passive"))
    )
    (net (code "81") (name "Net-(IC4-X1)") (class "Default")
      (node (ref "C16") (pin "2") (pinfunction "2_2") (pintype "passive"))
      (node (ref "IC4") (pin "24") (pinfunction "X1_24") (pintype "bidirectional"))
      (node (ref "X2") (pin "1") (pinfunction "1_1") (pintype "passive"))
    )
    (net (code "82") (name "Net-(IC5-ADC6)") (class "Default")
      (node (ref "A1") (pin "1") (pinfunction "1_1") (pintype "passive"))
      (node (ref "IC5") (pin "19") (pinfunction "ADC6_19") (pintype "bidirectional"))
    )
    (net (code "83") (name "Net-(IC5-ADC7)") (class "Default")
      (node (ref "A2") (pin "1") (pinfunction "1_1") (pintype "passive"))
      (node (ref "IC5") (pin "22") (pinfunction "ADC7_22") (pintype "bidirectional"))
    )
    (net (code "84") (name "Net-(IC5-PB6(XTAL1{slash}TOSC1))") (class "Default")
      (node (ref "C17") (pin "2") (pinfunction "2_2") (pintype "passive"))
      (node (ref "IC5") (pin "7") (pinfunction "PB6(XTAL1/TOSC1)_7") (pintype "bidirectional"))
      (node (ref "R9") (pin "2") (pinfunction "2_2") (pintype "passive"))
      (node (ref "X3") (pin "2") (pinfunction "2_2") (pintype "passive"))
    )
    (net (code "85") (name "Net-(IC5-PB7(XTAL2{slash}TOSC2))") (class "Default")
      (node (ref "C18") (pin "2") (pinfunction "2_2") (pintype "passive"))
      (node (ref "IC5") (pin "8") (pinfunction "PB7(XTAL2/TOSC2)_8") (pintype "bidirectional"))
      (node (ref "R9") (pin "1") (pinfunction "1_1") (pintype "passive"))
      (node (ref "X3") (pin "1") (pinfunction "1_1") (pintype "passive"))
    )
    (net (code "86") (name "Net-(L2-Pad1)") (class "Default")
      (node (ref "L2") (pin "1") (pinfunction "1_1") (pintype "passive"))
      (node (ref "P1") (pin "FIX1") (pinfunction "FIX1_FIX1") (pintype "bidirectional"))
      (node (ref "P1") (pin "FIX2") (pinfunction "FIX2_FIX2") (pintype "bidirectional"))
      (node (ref "P1") (pin "PIN1") (pinfunction "PIN1_PIN1") (pintype "bidirectional"))
      (node (ref "P1") (pin "PIN2") (pinfunction "PIN2_PIN2") (pintype "bidirectional"))
      (node (ref "P1") (pin "TAB1") (pinfunction "TAB1_TAB1") (pintype "bidirectional"))
      (node (ref "P1") (pin "TAB2") (pinfunction "TAB2_TAB2") (pintype "bidirectional"))
      (node (ref "Z1") (pin "2") (pinfunction "2_2") (pintype "passive"))
      (node (ref "Z2") (pin "2") (pinfunction "2_2") (pintype "passive"))
    )
    (net (code "87") (name "Net-(L3-Pad1)") (class "Default")
      (node (ref "L3") (pin "1") (pinfunction "1_1") (pintype "passive"))
      (node (ref "P3") (pin "SHELL1") (pinfunction "SHELL1_SHELL1") (pintype "passive"))
      (node (ref "P3") (pin "SHELL2") (pinfunction "SHELL2_SHELL2") (pintype "passive"))
    )
    (net (code "88") (name "Net-(LED2-PadC)") (class "Default")
      (node (ref "LED2") (pin "C") (pinfunction "C_C") (pintype "passive"))
      (node (ref "RN3") (pin "1") (pinfunction "1_1") (pintype "passive"))
    )
    (net (code "89") (name "Net-(LED4-PadA)") (class "Default")
      (node (ref "LED4") (pin "A") (pinfunction "A_A") (pintype "passive"))
      (node (ref "R5") (pin "1") (pinfunction "1_1") (pintype "passive"))
    )
    (net (code "90") (name "Net-(LED5-PadC)") (class "Default")
      (node (ref "LED5") (pin "C") (pinfunction "C_C") (pintype "passive"))
      (node (ref "R10") (pin "2") (pinfunction "2_2") (pintype "passive"))
    )
    (net (code "91") (name "Net-(P1-PadD+)") (class "Default")
      (node (ref "P1") (pin "D+") (pinfunction "D+_D+") (pintype "bidirectional"))
      (node (ref "R4") (pin "2") (pinfunction "2_2") (pintype "passive"))
      (node (ref "Z1") (pin "1") (pinfunction "1_1") (pintype "passive"))
    )
    (net (code "92") (name "Net-(P1-PadD-)") (class "Default")
      (node (ref "P1") (pin "D-") (pinfunction "D-_D-") (pintype "bidirectional"))
      (node (ref "R3") (pin "2") (pinfunction "2_2") (pintype "passive"))
      (node (ref "Z2") (pin "1") (pinfunction "1_1") (pintype "passive"))
    )
    (net (code "93") (name "Net-(P3-PadD+)") (class "Default")
      (node (ref "P3") (pin "D+") (pinfunction "D+_D+") (pintype "bidirectional"))
      (node (ref "R7") (pin "2") (pinfunction "2_2") (pintype "passive"))
    )
    (net (code "94") (name "Net-(P3-PadD-)") (class "Default")
      (node (ref "P3") (pin "D-") (pinfunction "D-_D-") (pintype "bidirectional"))
      (node (ref "R6") (pin "2") (pinfunction "2_2") (pintype "passive"))
    )
    (net (code "95") (name "Net-(P5-CS)") (class "Default")
      (node (ref "P5") (pin "2") (pinfunction "CS_2") (pintype "bidirectional"))
      (node (ref "RN2") (pin "4") (pinfunction "1_4") (pintype "passive"))
      (node (ref "RN4") (pin "8") (pinfunction "2_8") (pintype "passive"))
    )
    (net (code "96") (name "Net-(P5-DI)") (class "Default")
      (node (ref "P5") (pin "3") (pinfunction "DI_3") (pintype "bidirectional"))
      (node (ref "RN2") (pin "3") (pinfunction "1_3") (pintype "passive"))
      (node (ref "RN4") (pin "6") (pinfunction "2_6") (pintype "passive"))
    )
    (net (code "97") (name "Net-(P5-SCK)") (class "Default")
      (node (ref "P5") (pin "5") (pinfunction "SCK_5") (pintype "bidirectional"))
      (node (ref "RN2") (pin "2") (pinfunction "1_2") (pintype "passive"))
      (node (ref "RN4") (pin "7") (pinfunction "2_7") (pintype "passive"))
    )
    (net (code "98") (name "Net-(Q2-D)") (class "Default")
      (node (ref "Q2") (pin "3") (pinfunction "D_3") (pintype "passive"))
      (node (ref "R10") (pin "1") (pinfunction "1_1") (pintype "passive"))
    )
    (net (code "99") (name "Net-(RN2A-2)") (class "Default")
      (node (ref "LED1") (pin "C") (pinfunction "C_C") (pintype "passive"))
      (node (ref "RN2") (pin "8") (pinfunction "2_8") (pintype "passive"))
    )
    (net (code "100") (name "Net-(RN3B-1)") (class "Default")
      (node (ref "LED3") (pin "C") (pinfunction "C_C") (pintype "passive"))
      (node (ref "RN3") (pin "2") (pinfunction "1_2") (pintype "passive"))
    )
    (net (code "101") (name "unconnected-(H2-Pad1)") (class "Default")
      (node (ref "H2") (pin "1") (pinfunction "1_1") (pintype "passive"))
    )
    (net (code "102") (name "unconnected-(IC2-(RTS)PD6-Pad12)") (class "Default")
      (node (ref "IC2") (pin "12") (pinfunction "(RTS)PD6_12") (pintype "bidirectional"))
    )
    (net (code "103") (name "unconnected-(IC2-(SS)PB0-Pad14)") (class "Default")
      (node (ref "IC2") (pin "14") (pinfunction "(SS)PB0_14") (pintype "bidirectional"))
    )
    (net (code "104") (name "unconnected-(IC2-PB4-Pad18)") (class "Default")
      (node (ref "IC2") (pin "18") (pinfunction "PB4_18") (pintype "bidirectional"))
    )
    (net (code "105") (name "unconnected-(IC2-PB5-Pad19)") (class "Default")
      (node (ref "IC2") (pin "19") (pinfunction "PB5_19") (pintype "bidirectional"))
    )
    (net (code "106") (name "unconnected-(IC2-PB6-Pad20)") (class "Default")
      (node (ref "IC2") (pin "20") (pinfunction "PB6_20") (pintype "bidirectional"))
    )
    (net (code "107") (name "unconnected-(IC2-PB7-Pad21)") (class "Default")
      (node (ref "IC2") (pin "21") (pinfunction "PB7_21") (pintype "bidirectional"))
    )
    (net (code "108") (name "unconnected-(IC2-PC2-Pad5)") (class "Default")
      (node (ref "IC2") (pin "5") (pinfunction "PC2_5") (pintype "bidirectional"))
    )
    (net (code "109") (name "unconnected-(IC2-PC4-Pad26)") (class "Default")
      (node (ref "IC2") (pin "26") (pinfunction "PC4_26") (pintype "bidirectional"))
    )
    (net (code "110") (name "unconnected-(IC2-PC5-Pad25)") (class "Default")
      (node (ref "IC2") (pin "25") (pinfunction "PC5_25") (pintype "bidirectional"))
    )
    (net (code "111") (name "unconnected-(IC2-PC6-Pad23)") (class "Default")
      (node (ref "IC2") (pin "23") (pinfunction "PC6_23") (pintype "bidirectional"))
    )
    (net (code "112") (name "unconnected-(IC2-PC7-Pad22)") (class "Default")
      (node (ref "IC2") (pin "22") (pinfunction "PC7_22") (pintype "bidirectional"))
    )
    (net (code "113") (name "unconnected-(IC2-PD0-Pad6)") (class "Default")
      (node (ref "IC2") (pin "6") (pinfunction "PD0_6") (pintype "bidirectional"))
    )
    (net (code "114") (name "unconnected-(IC2-PD1-Pad7)") (class "Default")
      (node (ref "IC2") (pin "7") (pinfunction "PD1_7") (pintype "bidirectional"))
    )
    (net (code "115") (name "unconnected-(IC6-5A-Pad11)") (class "Default")
      (node (ref "IC6") (pin "11") (pinfunction "5A_11") (pintype "bidirectional"))
    )
    (net (code "116") (name "unconnected-(IC6-5Y-Pad12)") (class "Default")
      (node (ref "IC6") (pin "12") (pinfunction "5Y_12") (pintype "bidirectional"))
    )
    (net (code "117") (name "unconnected-(IC6-6A-Pad14)") (class "Default")
      (node (ref "IC6") (pin "14") (pinfunction "6A_14") (pintype "bidirectional"))
    )
    (net (code "118") (name "unconnected-(IC6-6Y-Pad15)") (class "Default")
      (node (ref "IC6") (pin "15") (pinfunction "6Y_15") (pintype "bidirectional"))
    )
    (net (code "119") (name "unconnected-(P1-PadID)") (class "Default")
      (node (ref "P1") (pin "ID") (pinfunction "ID_ID") (pintype "bidirectional"))
    )
    (net (code "120") (name "unconnected-(P5-NC-Pad1)") (class "Default")
      (node (ref "P5") (pin "1") (pinfunction "NC_1") (pintype "bidirectional"))
    )
    (net (code "121") (name "unconnected-(P5-RSV-Pad8)") (class "Default")
      (node (ref "P5") (pin "8") (pinfunction "RSV_8") (pintype "bidirectional"))
    )
    (net (code "122") (name "unconnected-(RN4D-1-Pad4)") (class "Default")
      (node (ref "RN4") (pin "4") (pinfunction "1_4") (pintype "passive"))
    )
    (net (code "123") (name "unconnected-(RN4D-2-Pad5)") (class "Default")
      (node (ref "RN4") (pin "5") (pinfunction "2_5") (pintype "passive"))
    )
  )
)
